# cpu_board.net
KiCad netlist of a schematic drawn in Altium Designer
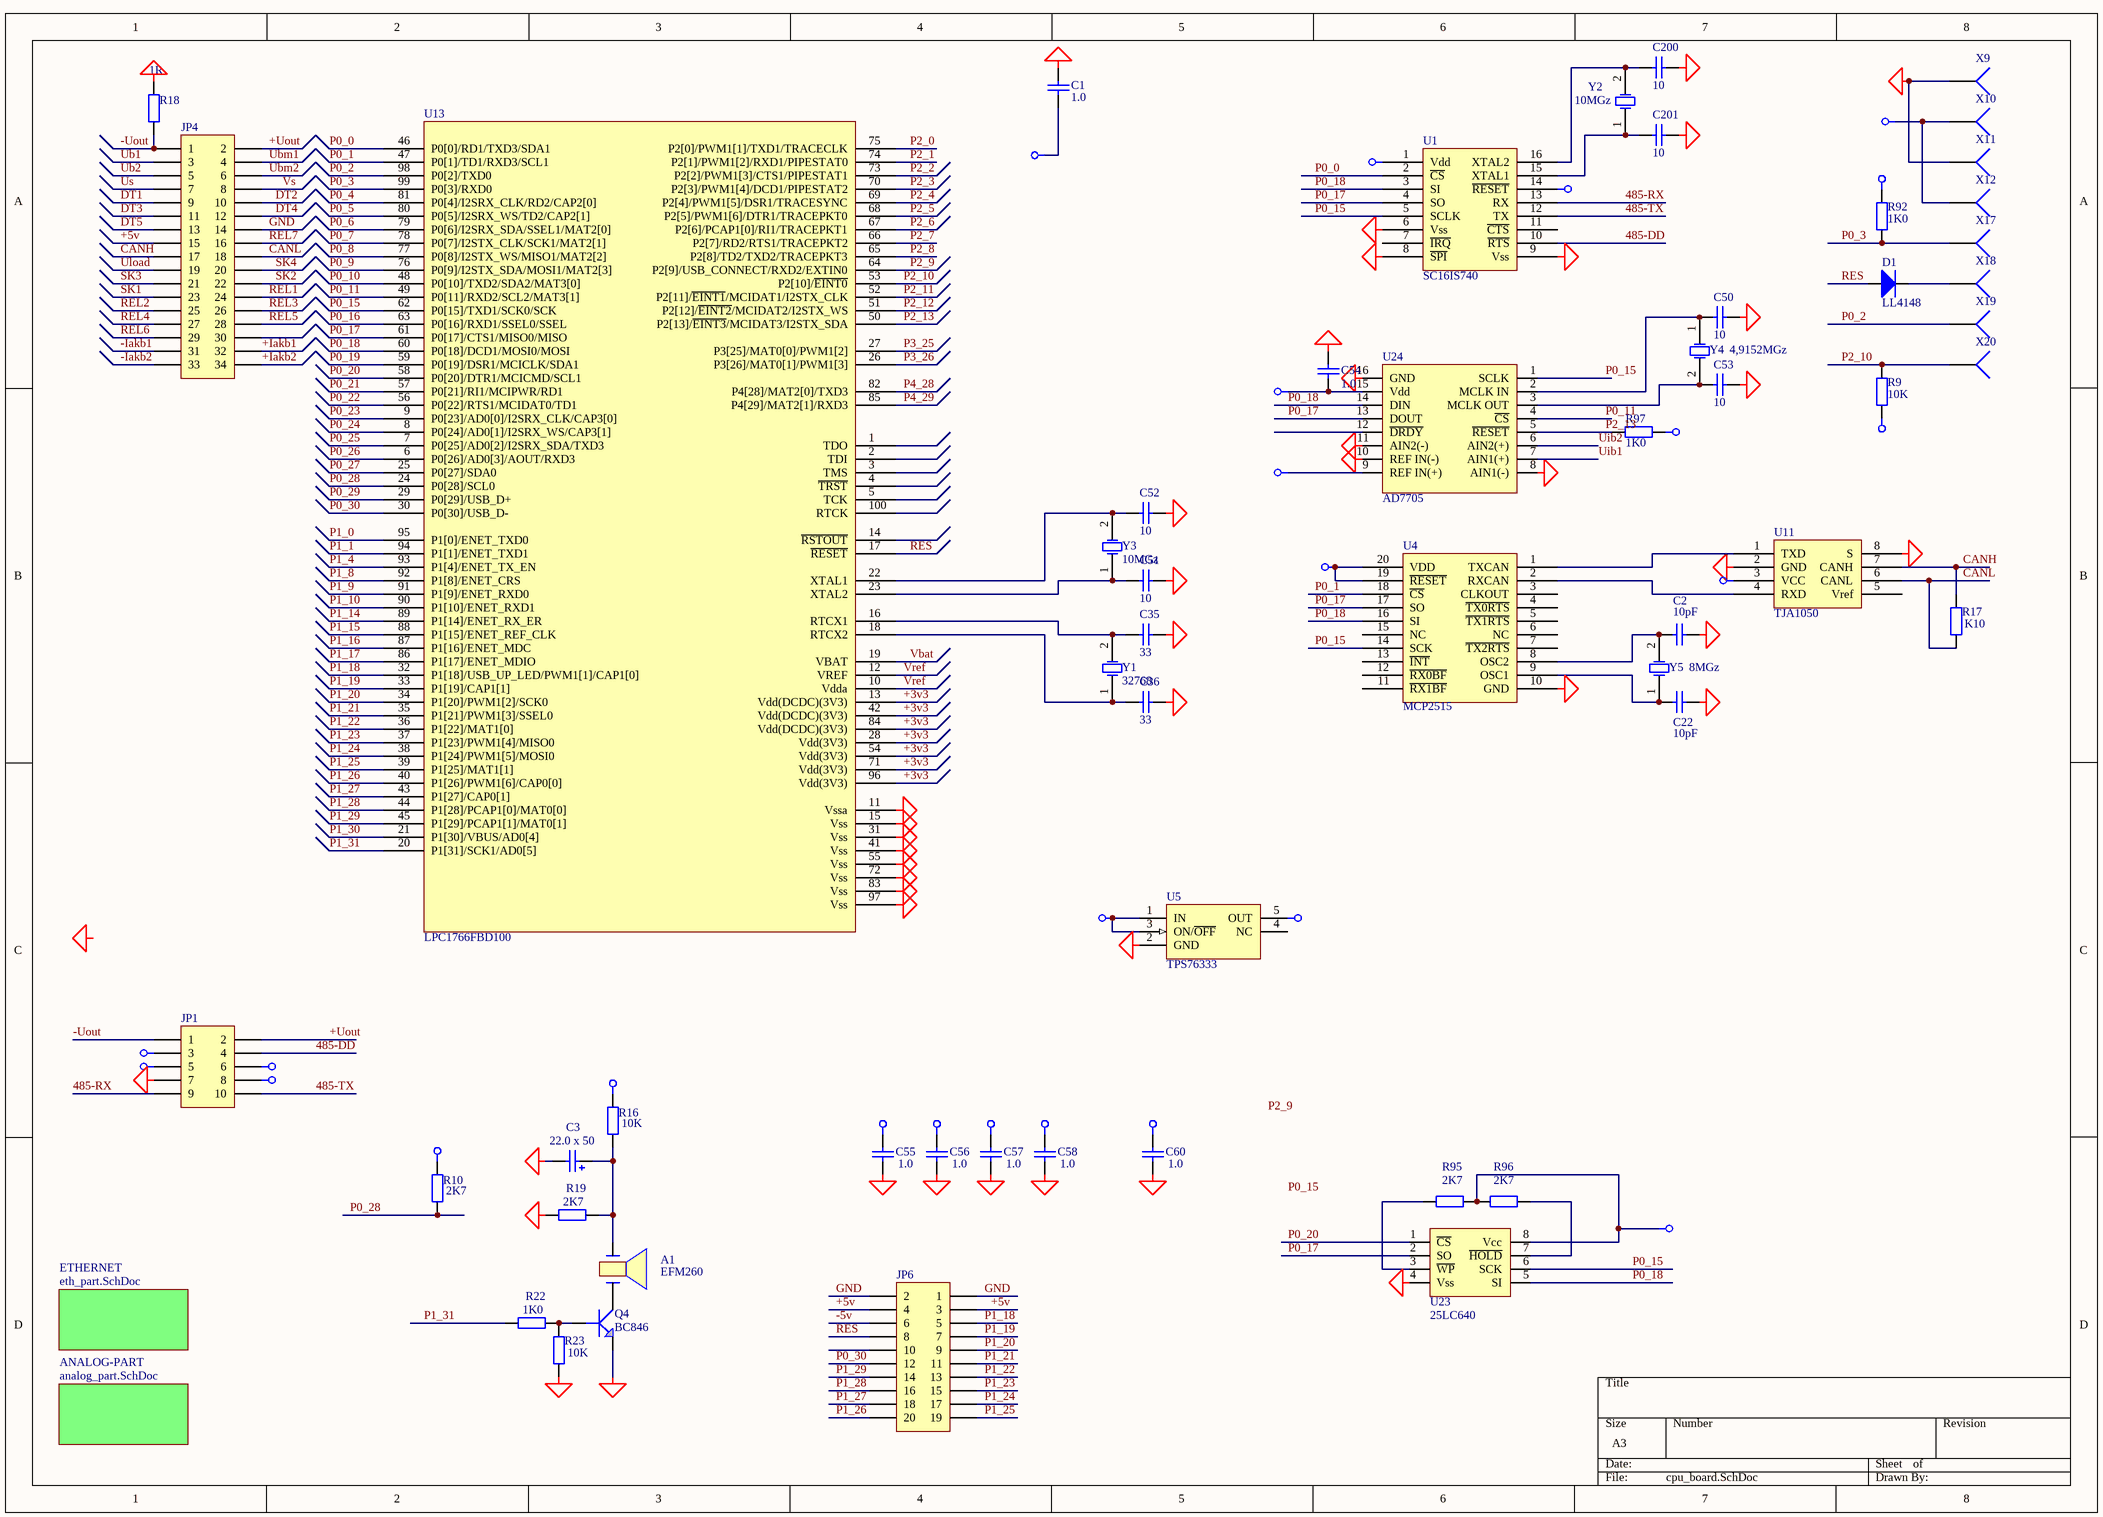
[diagram p0: cpu_board.SchDoc]

(export (version "E")
  (design (tool "Eeschema 10.0.6"))
  (components
    (comp (ref "A1")
      (value "EFM260")
      (footprint "Pjezo15")
      (description "Beeper")
      (libsource (lib "PAL") (part "PJEZ0"))
    )
    (comp (ref "C1")
      (value "1.0")
      (footprint "_1206")
      (description "Capacitor")
      (fields (field (name "MANUFACTURER") "Generic Components") (field (name "PUBLISHER") "Altium Limited"))
      (libsource (lib "Miscellaneous Devices") (part "Cap Semi"))
    )
    (comp (ref "C2")
      (value "Cap Semi")
      (footprint "_1206")
      (description "Capacitor (Semiconductor SIM Model)")
      (fields
        (field (name "MANUFACTURER") "Generic Components")
        (field (name "ALTIUM_VALUE") "10pF")
        (field (name "PUBLISHER") "Altium Limited")
      )
      (libsource (lib "Miscellaneous Devices") (part "Cap Semi"))
    )
    (comp (ref "C3")
      (value "22.0 x 50")
      (footprint "el3")
      (description "Polarized Capacitor (Radial)")
      (fields (field (name "MANUFACTURER") "Generic Components") (field (name "PUBLISHER") "Altium Limited"))
      (libsource (lib "PAL") (part "Cap Pol1"))
    )
    (comp (ref "C22")
      (value "Cap Semi")
      (footprint "_1206")
      (description "Capacitor (Semiconductor SIM Model)")
      (fields
        (field (name "MANUFACTURER") "Generic Components")
        (field (name "ALTIUM_VALUE") "10pF")
        (field (name "PUBLISHER") "Altium Limited")
      )
      (libsource (lib "Miscellaneous Devices") (part "Cap Semi"))
    )
    (comp (ref "C35")
      (value "33")
      (footprint "_1206")
      (description "Capacitor (Semiconductor SIM Model)")
      (fields (field (name "MANUFACTURER") "Generic Components") (field (name "PUBLISHER") "Altium Limited"))
      (libsource (lib "Miscellaneous Devices") (part "Cap Semi"))
    )
    (comp (ref "C36")
      (value "33")
      (footprint "_1206")
      (description "Capacitor (Semiconductor SIM Model)")
      (fields (field (name "MANUFACTURER") "Generic Components") (field (name "PUBLISHER") "Altium Limited"))
      (libsource (lib "Miscellaneous Devices") (part "Cap Semi"))
    )
    (comp (ref "C50")
      (value "10")
      (footprint "_1206")
      (description "Capacitor")
      (fields (field (name "MANUFACTURER") "Generic Components") (field (name "PUBLISHER") "Altium Limited"))
      (libsource (lib "") (part "Cap Semi_1"))
    )
    (comp (ref "C51")
      (value "10")
      (footprint "_1206")
      (description "Capacitor")
      (fields (field (name "MANUFACTURER") "Generic Components") (field (name "PUBLISHER") "Altium Limited"))
      (libsource (lib "Miscellaneous Devices") (part "Cap Semi"))
    )
    (comp (ref "C52")
      (value "10")
      (footprint "_1206")
      (description "Capacitor")
      (fields (field (name "MANUFACTURER") "Generic Components") (field (name "PUBLISHER") "Altium Limited"))
      (libsource (lib "Miscellaneous Devices") (part "Cap Semi"))
    )
    (comp (ref "C53")
      (value "10")
      (footprint "_1206")
      (description "Capacitor")
      (fields (field (name "MANUFACTURER") "Generic Components") (field (name "PUBLISHER") "Altium Limited"))
      (libsource (lib "") (part "Cap Semi_1"))
    )
    (comp (ref "C54")
      (value "1.0")
      (footprint "_1206")
      (description "Capacitor")
      (fields (field (name "MANUFACTURER") "Generic Components") (field (name "PUBLISHER") "Altium Limited"))
      (libsource (lib "Miscellaneous Devices") (part "Cap Semi"))
    )
    (comp (ref "C55")
      (value "1.0")
      (footprint "_1206")
      (description "Capacitor")
      (fields (field (name "MANUFACTURER") "Generic Components") (field (name "PUBLISHER") "Altium Limited"))
      (libsource (lib "Miscellaneous Devices") (part "Cap Semi"))
    )
    (comp (ref "C56")
      (value "1.0")
      (footprint "_1206")
      (description "Capacitor")
      (fields (field (name "MANUFACTURER") "Generic Components") (field (name "PUBLISHER") "Altium Limited"))
      (libsource (lib "Miscellaneous Devices") (part "Cap Semi"))
    )
    (comp (ref "C57")
      (value "1.0")
      (footprint "_1206")
      (description "Capacitor")
      (fields (field (name "MANUFACTURER") "Generic Components") (field (name "PUBLISHER") "Altium Limited"))
      (libsource (lib "Miscellaneous Devices") (part "Cap Semi"))
    )
    (comp (ref "C58")
      (value "1.0")
      (footprint "_1206")
      (description "Capacitor")
      (fields (field (name "MANUFACTURER") "Generic Components") (field (name "PUBLISHER") "Altium Limited"))
      (libsource (lib "Miscellaneous Devices") (part "Cap Semi"))
    )
    (comp (ref "C60")
      (value "1.0")
      (footprint "_1206")
      (description "Capacitor")
      (fields (field (name "MANUFACTURER") "Generic Components") (field (name "PUBLISHER") "Altium Limited"))
      (libsource (lib "Miscellaneous Devices") (part "Cap Semi"))
    )
    (comp (ref "C200")
      (value "10")
      (footprint "_1206")
      (description "Capacitor")
      (fields (field (name "MANUFACTURER") "Generic Components") (field (name "PUBLISHER") "Altium Limited"))
      (libsource (lib "Miscellaneous Devices") (part "Cap Semi"))
    )
    (comp (ref "C201")
      (value "10")
      (footprint "_1206")
      (description "Capacitor")
      (fields (field (name "MANUFACTURER") "Generic Components") (field (name "PUBLISHER") "Altium Limited"))
      (libsource (lib "Miscellaneous Devices") (part "Cap Semi"))
    )
    (comp (ref "D1")
      (value "LL4148")
      (footprint "_1206d")
      (description "Diode")
      (fields (field (name "MANUFACTURER") "Generic Components") (field (name "PUBLISHER") "Altium Limited"))
      (libsource (lib "PAL") (part "Diode"))
    )
    (comp (ref "JP1")
      (value "PBD-10")
      (footprint "HDR2X5")
      (description "Header, 5-Pin, Dual row")
      (fields (field (name "MANUFACTURER") "Generic Components") (field (name "PUBLISHER") "Altium Limited"))
      (libsource (lib "Miscellaneous Connectors") (part "Header 5X2"))
    )
    (comp (ref "JP4")
      (value "IDC34")
      (footprint "IDC34M")
      (description "Header, 17-Pin, Dual row")
      (fields (field (name "MANUFACTURER") "Generic Components") (field (name "PUBLISHER") "Altium Limited"))
      (libsource (lib "Miscellaneous Connectors") (part "Header 17X2"))
    )
    (comp (ref "JP6")
      (value "PBD-20")
      (footprint "HDR2X10")
      (description "Header, 10-Pin, Dual row")
      (fields (field (name "MANUFACTURER") "Generic Components") (field (name "PUBLISHER") "Altium Limited"))
      (libsource (lib "Miscellaneous Connectors") (part "Header 10X2"))
    )
    (comp (ref "Q4")
      (value "BC846")
      (footprint "SO-G3")
      (description "Bipolar transistor")
      (libsource (lib "MAIN") (part "GT122"))
    )
    (comp (ref "R9")
      (value "10K")
      (footprint "_1206")
      (description "Resistor")
      (fields (field (name "MANUFACTURER") "Generic Components") (field (name "PUBLISHER") "Altium Limited"))
      (libsource (lib "Miscellaneous Devices") (part "Res2"))
    )
    (comp (ref "R10")
      (value "2K7")
      (footprint "_1206")
      (description "Resistor")
      (fields (field (name "MANUFACTURER") "Generic Components") (field (name "PUBLISHER") "Altium Limited"))
      (libsource (lib "Miscellaneous Devices") (part "Res2"))
    )
    (comp (ref "R16")
      (value "10K")
      (footprint "_1206")
      (description "Resistor")
      (fields (field (name "MANUFACTURER") "Generic Components") (field (name "PUBLISHER") "Altium Limited"))
      (libsource (lib "Miscellaneous Devices") (part "Res2"))
    )
    (comp (ref "R17")
      (value "K10")
      (footprint "_1206")
      (description "Resistor")
      (fields (field (name "MANUFACTURER") "Generic Components") (field (name "PUBLISHER") "Altium Limited"))
      (libsource (lib "Miscellaneous Devices") (part "Res2"))
    )
    (comp (ref "R18")
      (value "1R")
      (footprint "_1206")
      (description "Resistor")
      (fields (field (name "MANUFACTURER") "Generic Components") (field (name "PUBLISHER") "Altium Limited"))
      (libsource (lib "Miscellaneous Devices") (part "Res2"))
    )
    (comp (ref "R19")
      (value "2K7")
      (footprint "_1206")
      (description "Resistor")
      (fields (field (name "MANUFACTURER") "Generic Components") (field (name "PUBLISHER") "Altium Limited"))
      (libsource (lib "") (part "Res2_1"))
    )
    (comp (ref "R22")
      (value "1K0")
      (footprint "_1206")
      (description "Resistor")
      (fields (field (name "MANUFACTURER") "Generic Components") (field (name "PUBLISHER") "Altium Limited"))
      (libsource (lib "") (part "Res2_1"))
    )
    (comp (ref "R23")
      (value "10K")
      (footprint "_1206")
      (description "Resistor")
      (fields (field (name "MANUFACTURER") "Generic Components") (field (name "PUBLISHER") "Altium Limited"))
      (libsource (lib "Miscellaneous Devices") (part "Res2"))
    )
    (comp (ref "R92")
      (value "1K0")
      (footprint "_1206")
      (description "Resistor")
      (fields (field (name "MANUFACTURER") "Generic Components") (field (name "PUBLISHER") "Altium Limited"))
      (libsource (lib "") (part "Res2_1"))
    )
    (comp (ref "R95")
      (value "2K7")
      (footprint "_1206")
      (description "Resistor")
      (fields (field (name "MANUFACTURER") "Generic Components") (field (name "PUBLISHER") "Altium Limited"))
      (libsource (lib "") (part "Res2_1"))
    )
    (comp (ref "R96")
      (value "2K7")
      (footprint "_1206")
      (description "Resistor")
      (fields (field (name "MANUFACTURER") "Generic Components") (field (name "PUBLISHER") "Altium Limited"))
      (libsource (lib "") (part "Res2_1"))
    )
    (comp (ref "R97")
      (value "1K0")
      (footprint "_1206")
      (description "Resistor")
      (fields (field (name "MANUFACTURER") "Generic Components") (field (name "PUBLISHER") "Altium Limited"))
      (libsource (lib "Miscellaneous Devices") (part "Res2"))
    )
    (comp (ref "U1") (value "SC16IS740") (footprint "SO-G16") (libsource (lib "PAL") (part "SC16IS740")))
    (comp (ref "U4")
      (value "MCP2515")
      (footprint "TSSO6X6-G20/D6.6")
      (libsource (lib "PAL") (part "MCP2515"))
    )
    (comp (ref "U5")
      (value "TPS76333")
      (footprint "SO-G5/P.95")
      (description "Voltage Regulator")
      (fields
        (field (name "MANUFACTURER") "National Semiconductor")
        (field (name "PUBLISHER") "Altium Limited")
      )
      (libsource (lib "NSC Power Mgt Voltage Regulator") (part "LP2980AIM5-3.3"))
    )
    (comp (ref "U11") (value "TJA1050") (footprint "SO-G8/D5") (libsource (lib "PAL") (part "TJA1050")))
    (comp (ref "U13")
      (value "LPC1766FBD100")
      (footprint "LPC2368")
      (libsource (lib "PAL") (part "LPC2368FBD100"))
    )
    (comp (ref "U23")
      (value "25LC640")
      (footprint "SO-G8/D5")
      (description "Memory")
      (libsource (lib "PAL") (part "25LC640"))
    )
    (comp (ref "U24")
      (value "AD7705")
      (footprint "SO-G16/D10.4")
      (description "ADC")
      (libsource (lib "PAL") (part "AD7705"))
    )
    (comp (ref "X9")
      (value "~")
      (footprint "PIN1")
      (description "Socket")
      (fields (field (name "MANUFACTURER") "Generic Components") (field (name "PUBLISHER") "Altium Limited"))
      (libsource (lib "Miscellaneous Connectors") (part "Socket"))
    )
    (comp (ref "X10")
      (value "~")
      (footprint "PIN1")
      (description "Socket")
      (fields (field (name "MANUFACTURER") "Generic Components") (field (name "PUBLISHER") "Altium Limited"))
      (libsource (lib "Miscellaneous Connectors") (part "Socket"))
    )
    (comp (ref "X11")
      (value "~")
      (footprint "PIN1")
      (description "Socket")
      (fields (field (name "MANUFACTURER") "Generic Components") (field (name "PUBLISHER") "Altium Limited"))
      (libsource (lib "Miscellaneous Connectors") (part "Socket"))
    )
    (comp (ref "X12")
      (value "~")
      (footprint "PIN1")
      (description "Socket")
      (fields (field (name "MANUFACTURER") "Generic Components") (field (name "PUBLISHER") "Altium Limited"))
      (libsource (lib "Miscellaneous Connectors") (part "Socket"))
    )
    (comp (ref "X17")
      (value "~")
      (footprint "PIN1")
      (description "Socket")
      (fields (field (name "MANUFACTURER") "Generic Components") (field (name "PUBLISHER") "Altium Limited"))
      (libsource (lib "Miscellaneous Connectors") (part "Socket"))
    )
    (comp (ref "X18")
      (value "~")
      (footprint "PIN1")
      (description "Socket")
      (fields (field (name "MANUFACTURER") "Generic Components") (field (name "PUBLISHER") "Altium Limited"))
      (libsource (lib "Miscellaneous Connectors") (part "Socket"))
    )
    (comp (ref "X19")
      (value "~")
      (footprint "PIN1")
      (description "Socket")
      (fields (field (name "MANUFACTURER") "Generic Components") (field (name "PUBLISHER") "Altium Limited"))
      (libsource (lib "Miscellaneous Connectors") (part "Socket"))
    )
    (comp (ref "X20")
      (value "~")
      (footprint "PIN1")
      (description "Socket")
      (fields (field (name "MANUFACTURER") "Generic Components") (field (name "PUBLISHER") "Altium Limited"))
      (libsource (lib "Miscellaneous Connectors") (part "Socket"))
    )
    (comp (ref "Y1")
      (value "32768")
      (footprint "QWARZ2")
      (description "Crystal Oscillator")
      (fields (field (name "MANUFACTURER") "Generic Components") (field (name "PUBLISHER") "Altium Limited"))
      (libsource (lib "Miscellaneous Devices") (part "XTAL"))
    )
    (comp (ref "Y2")
      (value "10MGz")
      (footprint "QWARZ1")
      (description "Crystal Oscillator")
      (fields (field (name "MANUFACTURER") "Generic Components") (field (name "PUBLISHER") "Altium Limited"))
      (libsource (lib "Miscellaneous Devices") (part "XTAL"))
    )
    (comp (ref "Y3")
      (value "10MGz")
      (footprint "QWARZ1")
      (description "Crystal Oscillator")
      (fields (field (name "MANUFACTURER") "Generic Components") (field (name "PUBLISHER") "Altium Limited"))
      (libsource (lib "Miscellaneous Devices") (part "XTAL"))
    )
    (comp (ref "Y4")
      (value "4,9152MGz")
      (footprint "QWARZ1")
      (description "Crystal Oscillator")
      (fields (field (name "MANUFACTURER") "Generic Components") (field (name "PUBLISHER") "Altium Limited"))
      (libsource (lib "") (part "XTAL_1"))
    )
    (comp (ref "Y5")
      (value "8MGz")
      (footprint "QWARZ1")
      (description "Crystal Oscillator")
      (fields (field (name "MANUFACTURER") "Generic Components") (field (name "PUBLISHER") "Altium Limited"))
      (libsource (lib "Miscellaneous Devices") (part "XTAL"))
    )
  )
  (nets
    (net (code "1") (name "+3v3") (class "Default")
      (node (ref "C1") (pin "1") (pinfunction "1_1") (pintype "passive"))
      (node (ref "C58") (pin "2") (pinfunction "2_2") (pintype "passive"))
      (node (ref "JP1") (pin "3") (pinfunction "3_3") (pintype "passive"))
      (node (ref "R10") (pin "2") (pinfunction "2_2") (pintype "passive"))
      (node (ref "R9") (pin "1") (pinfunction "1_1") (pintype "passive"))
      (node (ref "R92") (pin "2") (pinfunction "2_2") (pintype "passive"))
      (node (ref "U13") (pin "13") (pinfunction "Vdd(DCDC)(3V3)_13") (pintype "passive"))
      (node (ref "U13") (pin "28") (pinfunction "Vdd(3V3)_28") (pintype "passive"))
      (node (ref "U13") (pin "42") (pinfunction "Vdd(DCDC)(3V3)_42") (pintype "passive"))
      (node (ref "U13") (pin "54") (pinfunction "Vdd(3V3)_54") (pintype "passive"))
      (node (ref "U13") (pin "71") (pinfunction "Vdd(3V3)_71") (pintype "passive"))
      (node (ref "U13") (pin "84") (pinfunction "Vdd(DCDC)(3V3)_84") (pintype "passive"))
      (node (ref "U13") (pin "96") (pinfunction "Vdd(3V3)_96") (pintype "passive"))
    )
    (net (code "2") (name "+5v") (class "Default")
      (node (ref "C54") (pin "2") (pinfunction "2_2") (pintype "passive"))
      (node (ref "C55") (pin "2") (pinfunction "2_2") (pintype "passive"))
      (node (ref "C57") (pin "2") (pinfunction "2_2") (pintype "passive"))
      (node (ref "C60") (pin "2") (pinfunction "2_2") (pintype "passive"))
      (node (ref "JP1") (pin "5") (pinfunction "5_5") (pintype "passive"))
      (node (ref "JP4") (pin "15") (pinfunction "15_15") (pintype "passive"))
      (node (ref "JP6") (pin "3") (pinfunction "3_3") (pintype "passive"))
      (node (ref "JP6") (pin "4") (pinfunction "4_4") (pintype "passive"))
      (node (ref "R95") (pin "2") (pinfunction "2_2") (pintype "passive"))
      (node (ref "R96") (pin "1") (pinfunction "1_1") (pintype "passive"))
      (node (ref "R97") (pin "2") (pinfunction "2_2") (pintype "passive"))
      (node (ref "U1") (pin "1") (pinfunction "Vdd_1") (pintype "passive"))
      (node (ref "U1") (pin "14") (pinfunction "~{RESET}_14") (pintype "passive"))
      (node (ref "U11") (pin "3") (pinfunction "VCC_3") (pintype "passive"))
      (node (ref "U23") (pin "8") (pinfunction "Vcc_8") (pintype "passive"))
      (node (ref "U24") (pin "15") (pinfunction "Vdd_15") (pintype "passive"))
      (node (ref "U4") (pin "19") (pinfunction "~{RESET}_19") (pintype "passive"))
      (node (ref "U4") (pin "20") (pinfunction "VDD_20") (pintype "passive"))
      (node (ref "U5") (pin "1") (pinfunction "IN_1") (pintype "power_in"))
      (node (ref "U5") (pin "3") (pinfunction "ON/~{OFF}_3") (pintype "input"))
      (node (ref "X10") (pin "1") (pinfunction "1_1") (pintype "passive"))
      (node (ref "X12") (pin "1") (pinfunction "1_1") (pintype "passive"))
    )
    (net (code "3") (name "+Uout") (class "Default")
      (node (ref "JP1") (pin "2") (pinfunction "2_2") (pintype "passive"))
      (node (ref "JP4") (pin "2") (pinfunction "2_2") (pintype "passive"))
      (node (ref "R16") (pin "2") (pinfunction "2_2") (pintype "passive"))
    )
    (net (code "4") (name "-5v") (class "Default")
      (node (ref "C56") (pin "2") (pinfunction "2_2") (pintype "passive"))
      (node (ref "JP1") (pin "8") (pinfunction "8_8") (pintype "passive"))
      (node (ref "JP6") (pin "6") (pinfunction "6_6") (pintype "passive"))
    )
    (net (code "5") (name "/+Iakb1") (class "Default")
      (node (ref "JP4") (pin "32") (pinfunction "32_32") (pintype "passive"))
    )
    (net (code "6") (name "/+Iakb2") (class "Default")
      (node (ref "JP4") (pin "34") (pinfunction "34_34") (pintype "passive"))
    )
    (net (code "7") (name "/-Iakb1") (class "Default")
      (node (ref "JP4") (pin "31") (pinfunction "31_31") (pintype "passive"))
    )
    (net (code "8") (name "/-Iakb2") (class "Default")
      (node (ref "JP4") (pin "33") (pinfunction "33_33") (pintype "passive"))
    )
    (net (code "9") (name "/-Uout") (class "Default")
      (node (ref "JP1") (pin "1") (pinfunction "1_1") (pintype "passive"))
      (node (ref "JP4") (pin "1") (pinfunction "1_1") (pintype "passive"))
      (node (ref "R18") (pin "1") (pinfunction "1_1") (pintype "passive"))
    )
    (net (code "10") (name "/485-DD") (class "Default")
      (node (ref "JP1") (pin "4") (pinfunction "4_4") (pintype "passive"))
      (node (ref "U1") (pin "10") (pinfunction "~{RTS}_10") (pintype "passive"))
    )
    (net (code "11") (name "/485-RX") (class "Default")
      (node (ref "JP1") (pin "9") (pinfunction "9_9") (pintype "passive"))
      (node (ref "U1") (pin "13") (pinfunction "RX_13") (pintype "passive"))
    )
    (net (code "12") (name "/485-TX") (class "Default")
      (node (ref "JP1") (pin "10") (pinfunction "10_10") (pintype "passive"))
      (node (ref "U1") (pin "12") (pinfunction "TX_12") (pintype "passive"))
    )
    (net (code "13") (name "/CANH") (class "Default")
      (node (ref "JP4") (pin "17") (pinfunction "17_17") (pintype "passive"))
      (node (ref "R17") (pin "2") (pinfunction "2_2") (pintype "passive"))
      (node (ref "U11") (pin "7") (pinfunction "CANH_7") (pintype "passive"))
    )
    (net (code "14") (name "/CANL") (class "Default")
      (node (ref "JP4") (pin "18") (pinfunction "18_18") (pintype "passive"))
      (node (ref "R17") (pin "1") (pinfunction "1_1") (pintype "passive"))
      (node (ref "U11") (pin "6") (pinfunction "CANL_6") (pintype "passive"))
    )
    (net (code "15") (name "/DT1") (class "Default")
      (node (ref "JP4") (pin "9") (pinfunction "9_9") (pintype "passive"))
    )
    (net (code "16") (name "/DT2") (class "Default")
      (node (ref "JP4") (pin "10") (pinfunction "10_10") (pintype "passive"))
    )
    (net (code "17") (name "/DT3") (class "Default")
      (node (ref "JP4") (pin "11") (pinfunction "11_11") (pintype "passive"))
    )
    (net (code "18") (name "/DT4") (class "Default")
      (node (ref "JP4") (pin "12") (pinfunction "12_12") (pintype "passive"))
    )
    (net (code "19") (name "/DT5") (class "Default")
      (node (ref "JP4") (pin "13") (pinfunction "13_13") (pintype "passive"))
    )
    (net (code "20") (name "/P0_0") (class "Default")
      (node (ref "U1") (pin "2") (pinfunction "~{CS}_2") (pintype "passive"))
      (node (ref "U13") (pin "46") (pinfunction "P0[0]/RD1/TXD3/SDA1_46") (pintype "passive"))
    )
    (net (code "21") (name "/P0_1") (class "Default")
      (node (ref "U13") (pin "47") (pinfunction "P0[1]/TD1/RXD3/SCL1_47") (pintype "passive"))
      (node (ref "U4") (pin "18") (pinfunction "~{CS}_18") (pintype "passive"))
    )
    (net (code "22") (name "/P0_2") (class "Default")
      (node (ref "U13") (pin "98") (pinfunction "P0[2]/TXD0_98") (pintype "passive"))
      (node (ref "X19") (pin "1") (pinfunction "1_1") (pintype "passive"))
    )
    (net (code "23") (name "/P0_3") (class "Default")
      (node (ref "R92") (pin "1") (pinfunction "1_1") (pintype "passive"))
      (node (ref "U13") (pin "99") (pinfunction "P0[3]/RXD0_99") (pintype "passive"))
      (node (ref "X17") (pin "1") (pinfunction "1_1") (pintype "passive"))
    )
    (net (code "24") (name "/P0_4") (class "Default")
      (node (ref "U13") (pin "81") (pinfunction "P0[4]/I2SRX_CLK/RD2/CAP2[0]_81") (pintype "passive"))
    )
    (net (code "25") (name "/P0_5") (class "Default")
      (node (ref "U13") (pin "80") (pinfunction "P0[5]/I2SRX_WS/TD2/CAP2[1]_80") (pintype "passive"))
    )
    (net (code "26") (name "/P0_6") (class "Default")
      (node (ref "U13") (pin "79") (pinfunction "P0[6]/I2SRX_SDA/SSEL1/MAT2[0]_79") (pintype "passive"))
    )
    (net (code "27") (name "/P0_7") (class "Default")
      (node (ref "U13") (pin "78") (pinfunction "P0[7]/I2STX_CLK/SCK1/MAT2[1]_78") (pintype "passive"))
    )
    (net (code "28") (name "/P0_8") (class "Default")
      (node (ref "U13") (pin "77") (pinfunction "P0[8]/I2STX_WS/MISO1/MAT2[2]_77") (pintype "passive"))
    )
    (net (code "29") (name "/P0_9") (class "Default")
      (node (ref "U13") (pin "76") (pinfunction "P0[9]/I2STX_SDA/MOSI1/MAT2[3]_76") (pintype "passive"))
    )
    (net (code "30") (name "/P0_10") (class "Default")
      (node (ref "U13") (pin "48") (pinfunction "P0[10]/TXD2/SDA2/MAT3[0]_48") (pintype "passive"))
    )
    (net (code "31") (name "/P0_11") (class "Default")
      (node (ref "U13") (pin "49") (pinfunction "P0[11]/RXD2/SCL2/MAT3[1]_49") (pintype "passive"))
      (node (ref "U24") (pin "4") (pinfunction "~{CS}_4") (pintype "passive"))
    )
    (net (code "32") (name "/P0_15") (class "Default")
      (node (ref "U1") (pin "5") (pinfunction "SCLK_5") (pintype "passive"))
      (node (ref "U13") (pin "62") (pinfunction "P0[15]/TXD1/SCK0/SCK_62") (pintype "passive"))
      (node (ref "U23") (pin "6") (pinfunction "SCK_6") (pintype "passive"))
      (node (ref "U24") (pin "1") (pinfunction "SCLK_1") (pintype "passive"))
      (node (ref "U4") (pin "14") (pinfunction "SCK_14") (pintype "passive"))
    )
    (net (code "33") (name "/P0_16") (class "Default")
      (node (ref "U13") (pin "63") (pinfunction "P0[16]/RXD1/SSEL0/SSEL_63") (pintype "passive"))
    )
    (net (code "34") (name "/P0_17") (class "Default")
      (node (ref "U1") (pin "4") (pinfunction "SO_4") (pintype "passive"))
      (node (ref "U13") (pin "61") (pinfunction "P0[17]/CTS1/MISO0/MISO_61") (pintype "passive"))
      (node (ref "U23") (pin "2") (pinfunction "SO_2") (pintype "passive"))
      (node (ref "U24") (pin "13") (pinfunction "DOUT_13") (pintype "passive"))
      (node (ref "U4") (pin "17") (pinfunction "SO_17") (pintype "passive"))
    )
    (net (code "35") (name "/P0_18") (class "Default")
      (node (ref "U1") (pin "3") (pinfunction "SI_3") (pintype "passive"))
      (node (ref "U13") (pin "60") (pinfunction "P0[18]/DCD1/MOSI0/MOSI_60") (pintype "passive"))
      (node (ref "U23") (pin "5") (pinfunction "SI_5") (pintype "passive"))
      (node (ref "U24") (pin "14") (pinfunction "DIN_14") (pintype "passive"))
      (node (ref "U4") (pin "16") (pinfunction "SI_16") (pintype "passive"))
    )
    (net (code "36") (name "/P0_19") (class "Default")
      (node (ref "U13") (pin "59") (pinfunction "P0[19]/DSR1/MCICLK/SDA1_59") (pintype "passive"))
    )
    (net (code "37") (name "/P0_20") (class "Default")
      (node (ref "U13") (pin "58") (pinfunction "P0[20]/DTR1/MCICMD/SCL1_58") (pintype "passive"))
      (node (ref "U23") (pin "1") (pinfunction "~{CS}_1") (pintype "passive"))
    )
    (net (code "38") (name "/P0_21") (class "Default")
      (node (ref "U13") (pin "57") (pinfunction "P0[21]/RI1/MCIPWR/RD1_57") (pintype "passive"))
    )
    (net (code "39") (name "/P0_22") (class "Default")
      (node (ref "U13") (pin "56") (pinfunction "P0[22]/RTS1/MCIDAT0/TD1_56") (pintype "passive"))
    )
    (net (code "40") (name "/P0_23") (class "Default")
      (node (ref "U13") (pin "9") (pinfunction "P0[23]/AD0[0]/I2SRX_CLK/CAP3[0]_9") (pintype "passive"))
    )
    (net (code "41") (name "/P0_24") (class "Default")
      (node (ref "U13") (pin "8") (pinfunction "P0[24]/AD0[1]/I2SRX_WS/CAP3[1]_8") (pintype "passive"))
    )
    (net (code "42") (name "/P0_25") (class "Default")
      (node (ref "U13") (pin "7") (pinfunction "P0[25]/AD0[2]/I2SRX_SDA/TXD3_7") (pintype "passive"))
    )
    (net (code "43") (name "/P0_26") (class "Default")
      (node (ref "U13") (pin "6") (pinfunction "P0[26]/AD0[3]/AOUT/RXD3_6") (pintype "passive"))
    )
    (net (code "44") (name "/P0_27") (class "Default")
      (node (ref "U13") (pin "25") (pinfunction "P0[27]/SDA0_25") (pintype "passive"))
    )
    (net (code "45") (name "/P0_28") (class "Default")
      (node (ref "R10") (pin "1") (pinfunction "1_1") (pintype "passive"))
      (node (ref "U13") (pin "24") (pinfunction "P0[28]/SCL0_24") (pintype "passive"))
    )
    (net (code "46") (name "/P0_29") (class "Default")
      (node (ref "U13") (pin "29") (pinfunction "P0[29]/USB_D+_29") (pintype "passive"))
    )
    (net (code "47") (name "/P0_30") (class "Default")
      (node (ref "JP6") (pin "12") (pinfunction "12_12") (pintype "passive"))
      (node (ref "U13") (pin "30") (pinfunction "P0[30]/USB_D-_30") (pintype "passive"))
    )
    (net (code "48") (name "/P1_0") (class "Default")
      (node (ref "U13") (pin "95") (pinfunction "P1[0]/ENET_TXD0_95") (pintype "passive"))
    )
    (net (code "49") (name "/P1_1") (class "Default")
      (node (ref "U13") (pin "94") (pinfunction "P1[1]/ENET_TXD1_94") (pintype "passive"))
    )
    (net (code "50") (name "/P1_4") (class "Default")
      (node (ref "U13") (pin "93") (pinfunction "P1[4]/ENET_TX_EN_93") (pintype "passive"))
    )
    (net (code "51") (name "/P1_8") (class "Default")
      (node (ref "U13") (pin "92") (pinfunction "P1[8]/ENET_CRS_92") (pintype "passive"))
    )
    (net (code "52") (name "/P1_9") (class "Default")
      (node (ref "U13") (pin "91") (pinfunction "P1[9]/ENET_RXD0_91") (pintype "passive"))
    )
    (net (code "53") (name "/P1_10") (class "Default")
      (node (ref "U13") (pin "90") (pinfunction "P1[10]/ENET_RXD1_90") (pintype "passive"))
    )
    (net (code "54") (name "/P1_14") (class "Default")
      (node (ref "U13") (pin "89") (pinfunction "P1[14]/ENET_RX_ER_89") (pintype "passive"))
    )
    (net (code "55") (name "/P1_15") (class "Default")
      (node (ref "U13") (pin "88") (pinfunction "P1[15]/ENET_REF_CLK_88") (pintype "passive"))
    )
    (net (code "56") (name "/P1_16") (class "Default")
      (node (ref "U13") (pin "87") (pinfunction "P1[16]/ENET_MDC_87") (pintype "passive"))
    )
    (net (code "57") (name "/P1_17") (class "Default")
      (node (ref "U13") (pin "86") (pinfunction "P1[17]/ENET_MDIO_86") (pintype "passive"))
    )
    (net (code "58") (name "/P1_18") (class "Default")
      (node (ref "JP6") (pin "5") (pinfunction "5_5") (pintype "passive"))
      (node (ref "U13") (pin "32") (pinfunction "P1[18]/USB_UP_LED/PWM1[1]/CAP1[0]_32") (pintype "passive"))
    )
    (net (code "59") (name "/P1_19") (class "Default")
      (node (ref "JP6") (pin "7") (pinfunction "7_7") (pintype "passive"))
      (node (ref "U13") (pin "33") (pinfunction "P1[19]/CAP1[1]_33") (pintype "passive"))
    )
    (net (code "60") (name "/P1_20") (class "Default")
      (node (ref "JP6") (pin "9") (pinfunction "9_9") (pintype "passive"))
      (node (ref "U13") (pin "34") (pinfunction "P1[20]/PWM1[2]/SCK0_34") (pintype "passive"))
    )
    (net (code "61") (name "/P1_21") (class "Default")
      (node (ref "JP6") (pin "11") (pinfunction "11_11") (pintype "passive"))
      (node (ref "U13") (pin "35") (pinfunction "P1[21]/PWM1[3]/SSEL0_35") (pintype "passive"))
    )
    (net (code "62") (name "/P1_22") (class "Default")
      (node (ref "JP6") (pin "13") (pinfunction "13_13") (pintype "passive"))
      (node (ref "U13") (pin "36") (pinfunction "P1[22]/MAT1[0]_36") (pintype "passive"))
    )
    (net (code "63") (name "/P1_23") (class "Default")
      (node (ref "JP6") (pin "15") (pinfunction "15_15") (pintype "passive"))
      (node (ref "U13") (pin "37") (pinfunction "P1[23]/PWM1[4]/MISO0_37") (pintype "passive"))
    )
    (net (code "64") (name "/P1_24") (class "Default")
      (node (ref "JP6") (pin "17") (pinfunction "17_17") (pintype "passive"))
      (node (ref "U13") (pin "38") (pinfunction "P1[24]/PWM1[5]/MOSI0_38") (pintype "passive"))
    )
    (net (code "65") (name "/P1_25") (class "Default")
      (node (ref "JP6") (pin "19") (pinfunction "19_19") (pintype "passive"))
      (node (ref "U13") (pin "39") (pinfunction "P1[25]/MAT1[1]_39") (pintype "passive"))
    )
    (net (code "66") (name "/P1_26") (class "Default")
      (node (ref "JP6") (pin "20") (pinfunction "20_20") (pintype "passive"))
      (node (ref "U13") (pin "40") (pinfunction "P1[26]/PWM1[6]/CAP0[0]_40") (pintype "passive"))
    )
    (net (code "67") (name "/P1_27") (class "Default")
      (node (ref "JP6") (pin "18") (pinfunction "18_18") (pintype "passive"))
      (node (ref "U13") (pin "43") (pinfunction "P1[27]/CAP0[1]_43") (pintype "passive"))
    )
    (net (code "68") (name "/P1_28") (class "Default")
      (node (ref "JP6") (pin "16") (pinfunction "16_16") (pintype "passive"))
      (node (ref "U13") (pin "44") (pinfunction "P1[28]/PCAP1[0]/MAT0[0]_44") (pintype "passive"))
    )
    (net (code "69") (name "/P1_29") (class "Default")
      (node (ref "JP6") (pin "14") (pinfunction "14_14") (pintype "passive"))
      (node (ref "U13") (pin "45") (pinfunction "P1[29]/PCAP1[1]/MAT0[1]_45") (pintype "passive"))
    )
    (net (code "70") (name "/P1_30") (class "Default")
      (node (ref "U13") (pin "21") (pinfunction "P1[30]/VBUS/AD0[4]_21") (pintype "passive"))
    )
    (net (code "71") (name "/P1_31") (class "Default")
      (node (ref "R22") (pin "1") (pinfunction "1_1") (pintype "passive"))
      (node (ref "U13") (pin "20") (pinfunction "P1[31]/SCK1/AD0[5]_20") (pintype "passive"))
    )
    (net (code "72") (name "/P2_0") (class "Default")
      (node (ref "U13") (pin "75") (pinfunction "P2[0]/PWM1[1]/TXD1/TRACECLK_75") (pintype "passive"))
    )
    (net (code "73") (name "/P2_1") (class "Default")
      (node (ref "U13") (pin "74") (pinfunction "P2[1]/PWM1[2]/RXD1/PIPESTAT0_74") (pintype "passive"))
    )
    (net (code "74") (name "/P2_2") (class "Default")
      (node (ref "U13") (pin "73") (pinfunction "P2[2]/PWM1[3]/CTS1/PIPESTAT1_73") (pintype "passive"))
    )
    (net (code "75") (name "/P2_3") (class "Default")
      (node (ref "U13") (pin "70") (pinfunction "P2[3]/PWM1[4]/DCD1/PIPESTAT2_70") (pintype "passive"))
    )
    (net (code "76") (name "/P2_4") (class "Default")
      (node (ref "U13") (pin "69") (pinfunction "P2[4]/PWM1[5]/DSR1/TRACESYNC_69") (pintype "passive"))
    )
    (net (code "77") (name "/P2_5") (class "Default")
      (node (ref "U13") (pin "68") (pinfunction "P2[5]/PWM1[6]/DTR1/TRACEPKT0_68") (pintype "passive"))
    )
    (net (code "78") (name "/P2_6") (class "Default")
      (node (ref "U13") (pin "67") (pinfunction "P2[6]/PCAP1[0]/RI1/TRACEPKT1_67") (pintype "passive"))
    )
    (net (code "79") (name "/P2_7") (class "Default")
      (node (ref "U13") (pin "66") (pinfunction "P2[7]/RD2/RTS1/TRACEPKT2_66") (pintype "passive"))
    )
    (net (code "80") (name "/P2_8") (class "Default")
      (node (ref "U13") (pin "65") (pinfunction "P2[8]/TD2/TXD2/TRACEPKT3_65") (pintype "passive"))
    )
    (net (code "81") (name "/P2_9") (class "Default")
      (node (ref "U13") (pin "64") (pinfunction "P2[9]/USB_CONNECT/RXD2/EXTIN0_64") (pintype "passive"))
    )
    (net (code "82") (name "/P2_10") (class "Default")
      (node (ref "R9") (pin "2") (pinfunction "2_2") (pintype "passive"))
      (node (ref "U13") (pin "53") (pinfunction "P2[10]/~{EINT0}_53") (pintype "passive"))
      (node (ref "X20") (pin "1") (pinfunction "1_1") (pintype "passive"))
    )
    (net (code "83") (name "/P2_11") (class "Default")
      (node (ref "U13") (pin "52") (pinfunction "P2[11]/~{EINT1}/MCIDAT1/I2STX_CLK_52") (pintype "passive"))
    )
    (net (code "84") (name "/P2_12") (class "Default")
      (node (ref "U13") (pin "51") (pinfunction "P2[12]/~{EINT2}/MCIDAT2/I2STX_WS_51") (pintype "passive"))
    )
    (net (code "85") (name "/P2_13") (class "Default")
      (node (ref "R97") (pin "1") (pinfunction "1_1") (pintype "passive"))
      (node (ref "U13") (pin "50") (pinfunction "P2[13]/~{EINT3}/MCIDAT3/I2STX_SDA_50") (pintype "passive"))
      (node (ref "U24") (pin "5") (pinfunction "~{RESET}_5") (pintype "passive"))
    )
    (net (code "86") (name "/P3_25") (class "Default")
      (node (ref "U13") (pin "27") (pinfunction "P3[25]/MAT0[0]/PWM1[2]_27") (pintype "passive"))
    )
    (net (code "87") (name "/P3_26") (class "Default")
      (node (ref "U13") (pin "26") (pinfunction "P3[26]/MAT0[1]/PWM1[3]_26") (pintype "passive"))
    )
    (net (code "88") (name "/P4_28") (class "Default")
      (node (ref "U13") (pin "82") (pinfunction "P4[28]/MAT2[0]/TXD3_82") (pintype "passive"))
    )
    (net (code "89") (name "/P4_29") (class "Default")
      (node (ref "U13") (pin "85") (pinfunction "P4[29]/MAT2[1]/RXD3_85") (pintype "passive"))
    )
    (net (code "90") (name "/REL1") (class "Default")
      (node (ref "JP4") (pin "24") (pinfunction "24_24") (pintype "passive"))
    )
    (net (code "91") (name "/REL2") (class "Default")
      (node (ref "JP4") (pin "25") (pinfunction "25_25") (pintype "passive"))
    )
    (net (code "92") (name "/REL3") (class "Default")
      (node (ref "JP4") (pin "26") (pinfunction "26_26") (pintype "passive"))
    )
    (net (code "93") (name "/REL4") (class "Default")
      (node (ref "JP4") (pin "27") (pinfunction "27_27") (pintype "passive"))
    )
    (net (code "94") (name "/REL5") (class "Default")
      (node (ref "JP4") (pin "28") (pinfunction "28_28") (pintype "passive"))
    )
    (net (code "95") (name "/REL6") (class "Default")
      (node (ref "JP4") (pin "29") (pinfunction "29_29") (pintype "passive"))
    )
    (net (code "96") (name "/REL7") (class "Default")
      (node (ref "JP4") (pin "16") (pinfunction "16_16") (pintype "passive"))
    )
    (net (code "97") (name "/RES") (class "Default")
      (node (ref "D1") (pin "1") (pinfunction "A_1") (pintype "passive"))
      (node (ref "JP6") (pin "8") (pinfunction "8_8") (pintype "passive"))
      (node (ref "U13") (pin "17") (pinfunction "~{RESET}_17") (pintype "passive"))
    )
    (net (code "98") (name "/SK1") (class "Default")
      (node (ref "JP4") (pin "23") (pinfunction "23_23") (pintype "passive"))
    )
    (net (code "99") (name "/SK2") (class "Default")
      (node (ref "JP4") (pin "22") (pinfunction "22_22") (pintype "passive"))
    )
    (net (code "100") (name "/SK3") (class "Default")
      (node (ref "JP4") (pin "21") (pinfunction "21_21") (pintype "passive"))
    )
    (net (code "101") (name "/SK4") (class "Default")
      (node (ref "JP4") (pin "20") (pinfunction "20_20") (pintype "passive"))
    )
    (net (code "102") (name "/Ub1") (class "Default")
      (node (ref "JP4") (pin "3") (pinfunction "3_3") (pintype "passive"))
    )
    (net (code "103") (name "/Ub2") (class "Default")
      (node (ref "JP4") (pin "5") (pinfunction "5_5") (pintype "passive"))
    )
    (net (code "104") (name "/Ubm1") (class "Default")
      (node (ref "JP4") (pin "4") (pinfunction "4_4") (pintype "passive"))
    )
    (net (code "105") (name "/Ubm2") (class "Default")
      (node (ref "JP4") (pin "6") (pinfunction "6_6") (pintype "passive"))
    )
    (net (code "106") (name "/Uib1") (class "Default")
      (node (ref "U24") (pin "7") (pinfunction "AIN1(+)_7") (pintype "passive"))
    )
    (net (code "107") (name "/Uib2") (class "Default")
      (node (ref "U24") (pin "6") (pinfunction "AIN2(+)_6") (pintype "passive"))
    )
    (net (code "108") (name "/Uload") (class "Default")
      (node (ref "JP4") (pin "19") (pinfunction "19_19") (pintype "passive"))
    )
    (net (code "109") (name "/Us") (class "Default")
      (node (ref "JP4") (pin "7") (pinfunction "7_7") (pintype "passive"))
    )
    (net (code "110") (name "/Vs") (class "Default")
      (node (ref "JP4") (pin "8") (pinfunction "8_8") (pintype "passive"))
    )
    (net (code "111") (name "GND") (class "Default")
      (node (ref "C1") (pin "2") (pinfunction "2_2") (pintype "passive"))
      (node (ref "C2") (pin "1") (pinfunction "1_1") (pintype "passive"))
      (node (ref "C200") (pin "1") (pinfunction "1_1") (pintype "passive"))
      (node (ref "C201") (pin "1") (pinfunction "1_1") (pintype "passive"))
      (node (ref "C22") (pin "1") (pinfunction "1_1") (pintype "passive"))
      (node (ref "C3") (pin "2") (pinfunction "2_2") (pintype "passive"))
      (node (ref "C35") (pin "1") (pinfunction "1_1") (pintype "passive"))
      (node (ref "C36") (pin "1") (pinfunction "1_1") (pintype "passive"))
      (node (ref "C50") (pin "1") (pinfunction "1_1") (pintype "passive"))
      (node (ref "C51") (pin "1") (pinfunction "1_1") (pintype "passive"))
      (node (ref "C52") (pin "1") (pinfunction "1_1") (pintype "passive"))
      (node (ref "C53") (pin "1") (pinfunction "1_1") (pintype "passive"))
      (node (ref "C54") (pin "1") (pinfunction "1_1") (pintype "passive"))
      (node (ref "C55") (pin "1") (pinfunction "1_1") (pintype "passive"))
      (node (ref "C56") (pin "1") (pinfunction "1_1") (pintype "passive"))
      (node (ref "C57") (pin "1") (pinfunction "1_1") (pintype "passive"))
      (node (ref "C58") (pin "1") (pinfunction "1_1") (pintype "passive"))
      (node (ref "C60") (pin "1") (pinfunction "1_1") (pintype "passive"))
      (node (ref "JP1") (pin "7") (pinfunction "7_7") (pintype "passive"))
      (node (ref "JP4") (pin "14") (pinfunction "14_14") (pintype "passive"))
      (node (ref "JP6") (pin "1") (pinfunction "1_1") (pintype "passive"))
      (node (ref "JP6") (pin "2") (pinfunction "2_2") (pintype "passive"))
      (node (ref "Q4") (pin "2") (pinfunction "E_2") (pintype "passive"))
      (node (ref "R18") (pin "2") (pinfunction "2_2") (pintype "passive"))
      (node (ref "R19") (pin "1") (pinfunction "1_1") (pintype "passive"))
      (node (ref "R23") (pin "1") (pinfunction "1_1") (pintype "passive"))
      (node (ref "U1") (pin "6") (pinfunction "Vss_6") (pintype "passive"))
      (node (ref "U1") (pin "8") (pinfunction "~{SPI}_8") (pintype "passive"))
      (node (ref "U1") (pin "9") (pinfunction "Vss_9") (pintype "passive"))
      (node (ref "U11") (pin "2") (pinfunction "GND_2") (pintype "passive"))
      (node (ref "U11") (pin "8") (pinfunction "S_8") (pintype "passive"))
      (node (ref "U13") (pin "11") (pinfunction "Vssa_11") (pintype "passive"))
      (node (ref "U13") (pin "15") (pinfunction "Vss_15") (pintype "passive"))
      (node (ref "U13") (pin "31") (pinfunction "Vss_31") (pintype "passive"))
      (node (ref "U13") (pin "41") (pinfunction "Vss_41") (pintype "passive"))
      (node (ref "U13") (pin "55") (pinfunction "Vss_55") (pintype "passive"))
      (node (ref "U13") (pin "72") (pinfunction "Vss_72") (pintype "passive"))
      (node (ref "U13") (pin "83") (pinfunction "Vss_83") (pintype "passive"))
      (node (ref "U13") (pin "97") (pinfunction "Vss_97") (pintype "passive"))
      (node (ref "U23") (pin "4") (pinfunction "Vss_4") (pintype "passive"))
      (node (ref "U24") (pin "10") (pinfunction "REF_IN(-)_10") (pintype "passive"))
      (node (ref "U24") (pin "11") (pinfunction "AIN2(-)_11") (pintype "passive"))
      (node (ref "U24") (pin "16") (pinfunction "GND_16") (pintype "passive"))
      (node (ref "U24") (pin "8") (pinfunction "AIN1(-)_8") (pintype "passive"))
      (node (ref "U4") (pin "10") (pinfunction "GND_10") (pintype "passive"))
      (node (ref "U5") (pin "2") (pinfunction "GND_2") (pintype "power_in"))
      (node (ref "X11") (pin "1") (pinfunction "1_1") (pintype "passive"))
      (node (ref "X9") (pin "1") (pinfunction "1_1") (pintype "passive"))
    )
    (net (code "112") (name "Net-(A1-Pad2)") (class "Default")
      (node (ref "A1") (pin "2") (pinfunction "2_2") (pintype "passive"))
      (node (ref "C3") (pin "1") (pinfunction "1_1") (pintype "passive"))
      (node (ref "R16") (pin "1") (pinfunction "1_1") (pintype "passive"))
      (node (ref "R19") (pin "2") (pinfunction "2_2") (pintype "passive"))
    )
    (net (code "113") (name "Net-(D1-K)") (class "Default")
      (node (ref "D1") (pin "2") (pinfunction "K_2") (pintype "passive"))
      (node (ref "X18") (pin "1") (pinfunction "1_1") (pintype "passive"))
    )
    (net (code "114") (name "Net-(Q4-B)") (class "Default")
      (node (ref "Q4") (pin "1") (pinfunction "B_1") (pintype "passive"))
      (node (ref "R22") (pin "2") (pinfunction "2_2") (pintype "passive"))
      (node (ref "R23") (pin "2") (pinfunction "2_2") (pintype "passive"))
    )
    (net (code "115") (name "Net-(Q4-C)") (class "Default")
      (node (ref "A1") (pin "1") (pinfunction "1_1") (pintype "passive"))
      (node (ref "Q4") (pin "3") (pinfunction "C_3") (pintype "passive"))
    )
    (net (code "116") (name "Net-(U1-XTAL1)") (class "Default")
      (node (ref "C201") (pin "2") (pinfunction "2_2") (pintype "passive"))
      (node (ref "U1") (pin "15") (pinfunction "XTAL1_15") (pintype "passive"))
      (node (ref "Y2") (pin "1") (pinfunction "OSC1_1") (pintype "passive"))
    )
    (net (code "117") (name "Net-(U1-XTAL2)") (class "Default")
      (node (ref "C200") (pin "2") (pinfunction "2_2") (pintype "passive"))
      (node (ref "U1") (pin "16") (pinfunction "XTAL2_16") (pintype "passive"))
      (node (ref "Y2") (pin "2") (pinfunction "OSC2_2") (pintype "passive"))
    )
    (net (code "118") (name "Net-(U4-OSC1)") (class "Default")
      (node (ref "C22") (pin "2") (pinfunction "2_2") (pintype "passive"))
      (node (ref "U4") (pin "9") (pinfunction "OSC1_9") (pintype "passive"))
      (node (ref "Y5") (pin "1") (pinfunction "OSC1_1") (pintype "passive"))
    )
    (net (code "119") (name "Net-(U4-OSC2)") (class "Default")
      (node (ref "C2") (pin "2") (pinfunction "2_2") (pintype "passive"))
      (node (ref "U4") (pin "8") (pinfunction "OSC2_8") (pintype "passive"))
      (node (ref "Y5") (pin "2") (pinfunction "OSC2_2") (pintype "passive"))
    )
    (net (code "120") (name "Net-(U11-RXD)") (class "Default")
      (node (ref "U11") (pin "4") (pinfunction "RXD_4") (pintype "passive"))
      (node (ref "U4") (pin "2") (pinfunction "RXCAN_2") (pintype "passive"))
    )
    (net (code "121") (name "Net-(U11-TXD)") (class "Default")
      (node (ref "U11") (pin "1") (pinfunction "TXD_1") (pintype "passive"))
      (node (ref "U4") (pin "1") (pinfunction "TXCAN_1") (pintype "passive"))
    )
    (net (code "122") (name "Net-(U13-RTCX1)") (class "Default")
      (node (ref "C35") (pin "2") (pinfunction "2_2") (pintype "passive"))
      (node (ref "U13") (pin "16") (pinfunction "RTCX1_16") (pintype "passive"))
      (node (ref "Y1") (pin "2") (pinfunction "OSC2_2") (pintype "passive"))
    )
    (net (code "123") (name "Net-(U13-RTCX2)") (class "Default")
      (node (ref "C36") (pin "2") (pinfunction "2_2") (pintype "passive"))
      (node (ref "U13") (pin "18") (pinfunction "RTCX2_18") (pintype "passive"))
      (node (ref "Y1") (pin "1") (pinfunction "OSC1_1") (pintype "passive"))
    )
    (net (code "124") (name "Net-(U13-XTAL1)") (class "Default")
      (node (ref "C52") (pin "2") (pinfunction "2_2") (pintype "passive"))
      (node (ref "U13") (pin "22") (pinfunction "XTAL1_22") (pintype "passive"))
      (node (ref "Y3") (pin "2") (pinfunction "OSC2_2") (pintype "passive"))
    )
    (net (code "125") (name "Net-(U13-XTAL2)") (class "Default")
      (node (ref "C51") (pin "2") (pinfunction "2_2") (pintype "passive"))
      (node (ref "U13") (pin "23") (pinfunction "XTAL2_23") (pintype "passive"))
      (node (ref "Y3") (pin "1") (pinfunction "OSC1_1") (pintype "passive"))
    )
    (net (code "126") (name "Net-(U23-~{HOLD})") (class "Default")
      (node (ref "R96") (pin "2") (pinfunction "2_2") (pintype "passive"))
      (node (ref "U23") (pin "7") (pinfunction "~{HOLD}_7") (pintype "passive"))
    )
    (net (code "127") (name "Net-(U23-~{WP})") (class "Default")
      (node (ref "R95") (pin "1") (pinfunction "1_1") (pintype "passive"))
      (node (ref "U23") (pin "3") (pinfunction "~{WP}_3") (pintype "passive"))
    )
    (net (code "128") (name "Net-(U24-MCLK_IN)") (class "Default")
      (node (ref "C50") (pin "2") (pinfunction "2_2") (pintype "passive"))
      (node (ref "U24") (pin "2") (pinfunction "MCLK_IN_2") (pintype "passive"))
      (node (ref "Y4") (pin "1") (pinfunction "OSC1_1") (pintype "passive"))
    )
    (net (code "129") (name "Net-(U24-MCLK_OUT)") (class "Default")
      (node (ref "C53") (pin "2") (pinfunction "2_2") (pintype "passive"))
      (node (ref "U24") (pin "3") (pinfunction "MCLK_OUT_3") (pintype "passive"))
      (node (ref "Y4") (pin "2") (pinfunction "OSC2_2") (pintype "passive"))
    )
    (net (code "130") (name "Vbat") (class "Default")
      (node (ref "JP1") (pin "6") (pinfunction "6_6") (pintype "passive"))
      (node (ref "U13") (pin "19") (pinfunction "VBAT_19") (pintype "passive"))
    )
    (net (code "131") (name "Vref") (class "Default")
      (node (ref "U13") (pin "10") (pinfunction "Vdda_10") (pintype "passive"))
      (node (ref "U13") (pin "12") (pinfunction "VREF_12") (pintype "passive"))
      (node (ref "U24") (pin "9") (pinfunction "REF_IN(+)_9") (pintype "passive"))
      (node (ref "U5") (pin "5") (pinfunction "OUT_5") (pintype "power_in"))
    )
    (net (code "132") (name "unconnected-(JP4-Pad30)") (class "Default")
      (node (ref "JP4") (pin "30") (pinfunction "30_30") (pintype "passive"))
    )
    (net (code "133") (name "unconnected-(JP6-Pad10)") (class "Default")
      (node (ref "JP6") (pin "10") (pinfunction "10_10") (pintype "passive"))
    )
    (net (code "134") (name "unconnected-(U1-~{CTS}-Pad11)") (class "Default")
      (node (ref "U1") (pin "11") (pinfunction "~{CTS}_11") (pintype "passive"))
    )
    (net (code "135") (name "unconnected-(U1-~{IRQ}-Pad7)") (class "Default")
      (node (ref "U1") (pin "7") (pinfunction "~{IRQ}_7") (pintype "passive"))
    )
    (net (code "136") (name "unconnected-(U4-CLKOUT-Pad3)") (class "Default")
      (node (ref "U4") (pin "3") (pinfunction "CLKOUT_3") (pintype "passive"))
    )
    (net (code "137") (name "unconnected-(U4-NC-Pad6)") (class "Default")
      (node (ref "U4") (pin "6") (pinfunction "NC_6") (pintype "passive"))
    )
    (net (code "138") (name "unconnected-(U4-NC-Pad15)") (class "Default")
      (node (ref "U4") (pin "15") (pinfunction "NC_15") (pintype "passive"))
    )
    (net (code "139") (name "unconnected-(U4-~{INT}-Pad13)") (class "Default")
      (node (ref "U4") (pin "13") (pinfunction "~{INT}_13") (pintype "passive"))
    )
    (net (code "140") (name "unconnected-(U4-~{RX0BF}-Pad12)") (class "Default")
      (node (ref "U4") (pin "12") (pinfunction "~{RX0BF}_12") (pintype "passive"))
    )
    (net (code "141") (name "unconnected-(U4-~{RX1BF}-Pad11)") (class "Default")
      (node (ref "U4") (pin "11") (pinfunction "~{RX1BF}_11") (pintype "passive"))
    )
    (net (code "142") (name "unconnected-(U4-~{TX0RTS}-Pad4)") (class "Default")
      (node (ref "U4") (pin "4") (pinfunction "~{TX0RTS}_4") (pintype "passive"))
    )
    (net (code "143") (name "unconnected-(U4-~{TX1RTS}-Pad5)") (class "Default")
      (node (ref "U4") (pin "5") (pinfunction "~{TX1RTS}_5") (pintype "passive"))
    )
    (net (code "144") (name "unconnected-(U4-~{TX2RTS}-Pad7)") (class "Default")
      (node (ref "U4") (pin "7") (pinfunction "~{TX2RTS}_7") (pintype "passive"))
    )
    (net (code "145") (name "unconnected-(U5-NC-Pad4)") (class "Default")
      (node (ref "U5") (pin "4") (pinfunction "NC_4") (pintype "passive"))
    )
    (net (code "146") (name "unconnected-(U11-Vref-Pad5)") (class "Default")
      (node (ref "U11") (pin "5") (pinfunction "Vref_5") (pintype "passive"))
    )
    (net (code "147") (name "unconnected-(U13-RTCK-Pad100)") (class "Default")
      (node (ref "U13") (pin "100") (pinfunction "RTCK_100") (pintype "passive"))
    )
    (net (code "148") (name "unconnected-(U13-TCK-Pad5)") (class "Default")
      (node (ref "U13") (pin "5") (pinfunction "TCK_5") (pintype "passive"))
    )
    (net (code "149") (name "unconnected-(U13-TDI-Pad2)") (class "Default")
      (node (ref "U13") (pin "2") (pinfunction "TDI_2") (pintype "passive"))
    )
    (net (code "150") (name "unconnected-(U13-TDO-Pad1)") (class "Default")
      (node (ref "U13") (pin "1") (pinfunction "TDO_1") (pintype "passive"))
    )
    (net (code "151") (name "unconnected-(U13-TMS-Pad3)") (class "Default")
      (node (ref "U13") (pin "3") (pinfunction "TMS_3") (pintype "passive"))
    )
    (net (code "152") (name "unconnected-(U13-~{RSTOUT}-Pad14)") (class "Default")
      (node (ref "U13") (pin "14") (pinfunction "~{RSTOUT}_14") (pintype "passive"))
    )
    (net (code "153") (name "unconnected-(U13-~{TRST}-Pad4)") (class "Default")
      (node (ref "U13") (pin "4") (pinfunction "~{TRST}_4") (pintype "passive"))
    )
    (net (code "154") (name "unconnected-(U24-~{DRDY}-Pad12)") (class "Default")
      (node (ref "U24") (pin "12") (pinfunction "~{DRDY}_12") (pintype "passive"))
    )
  )
)
